# MyPulseSensorTH.net
KiCad netlist of a schematic drawn in EAGLE
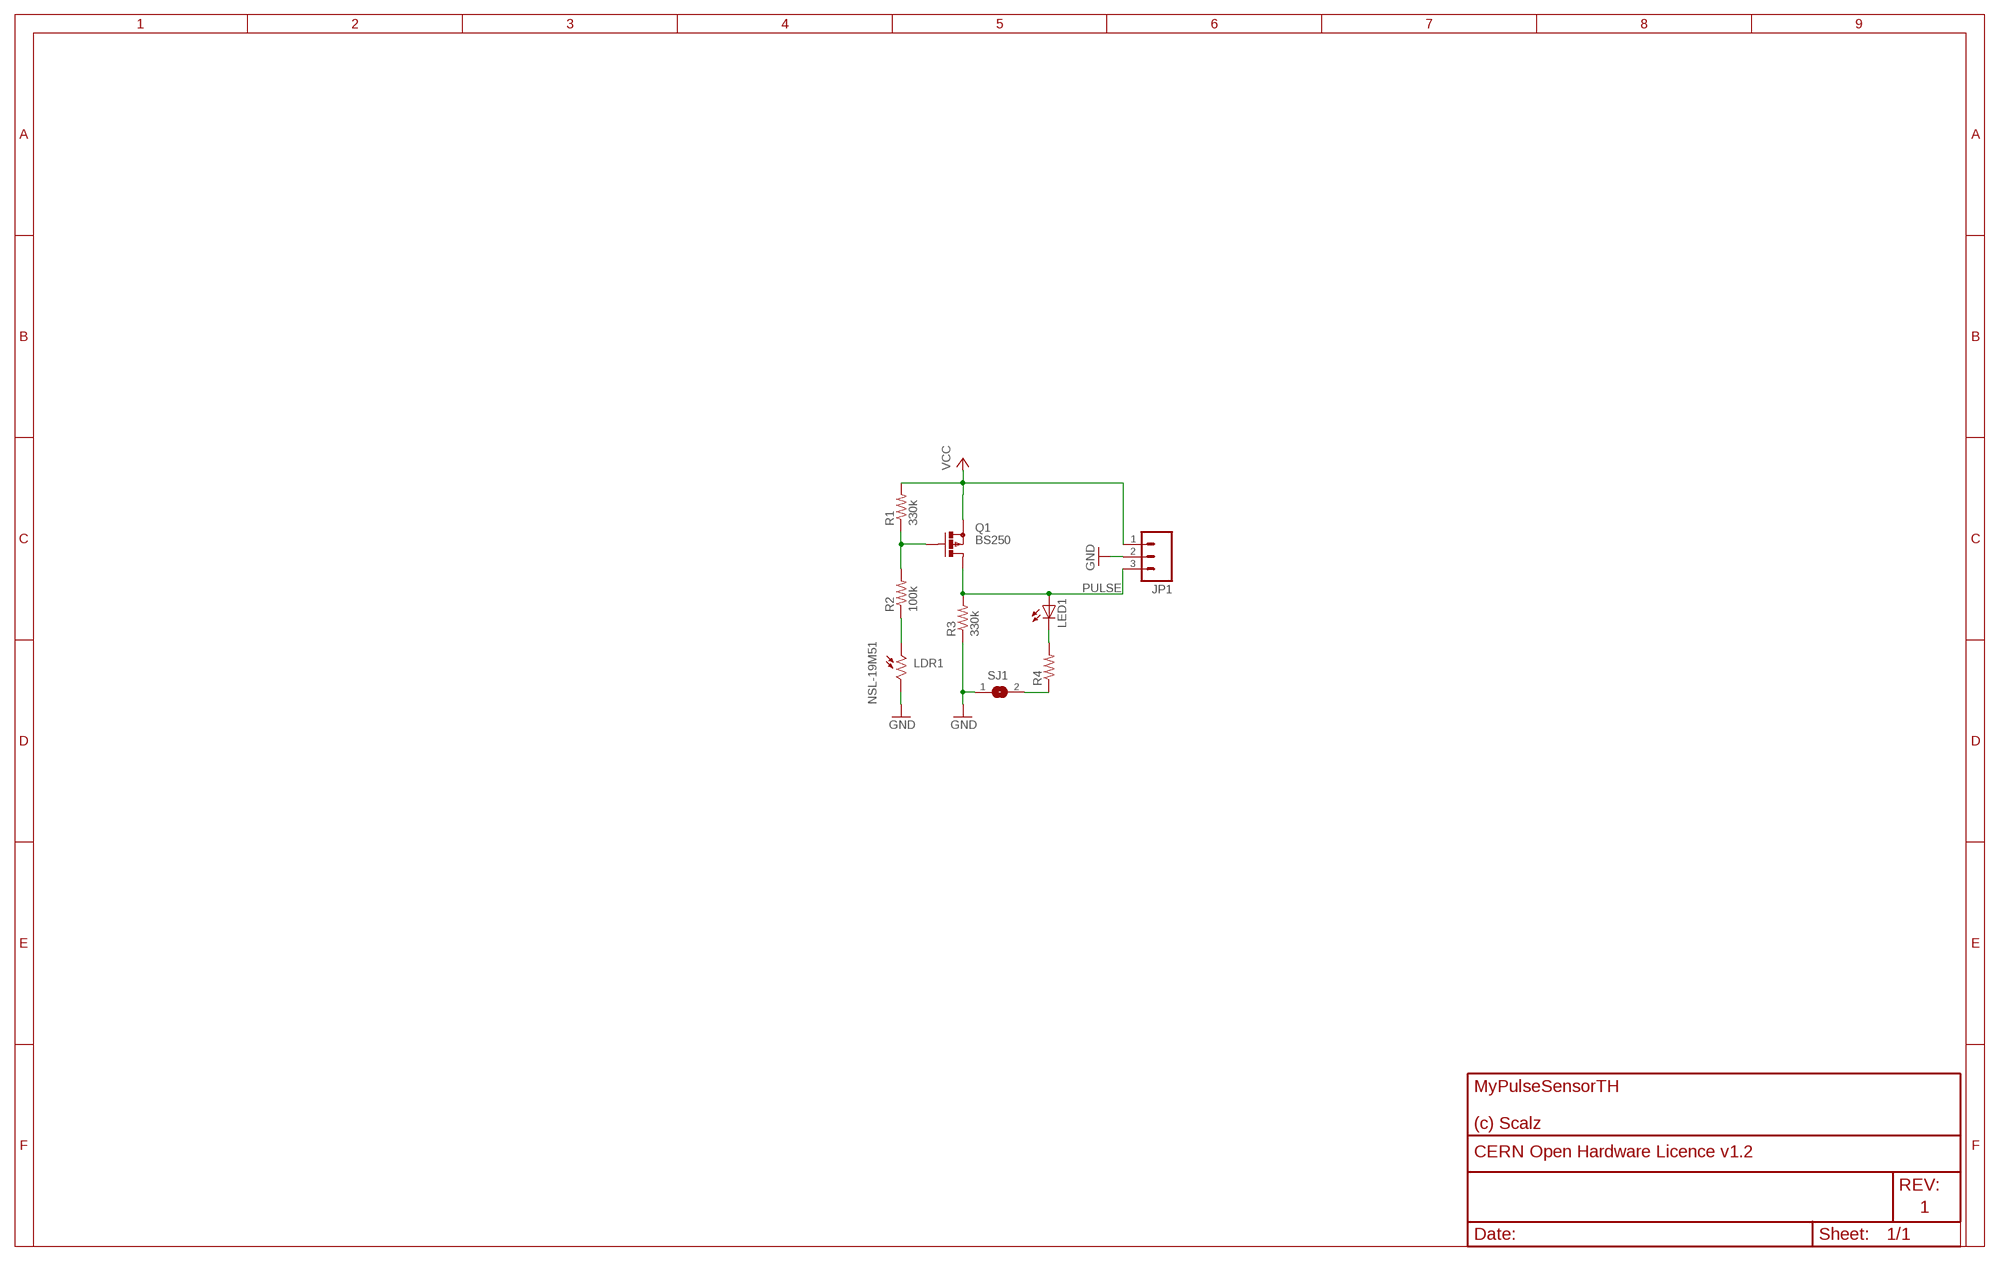
[diagram p0: schematic, sheet 1]

(export (version "E")
  (design (tool "Eeschema 10.0.6"))
  (components
    (comp (ref "JP1")
      (value "M03PTH")
      (footprint "eagle-import:1X03")
      (libsource (lib "eagle-import") (part "M03PTH"))
    )
    (comp (ref "LDR1")
      (value "NSL-19M51")
      (footprint "eagle-import:PHOTORESISTOR_TO18")
      (libsource (lib "eagle-import") (part "NSL-19M51"))
    )
    (comp (ref "LED1")
      (value "LED5MM")
      (footprint "eagle-import:LED5MM")
      (libsource (lib "eagle-import") (part "LED5MM"))
    )
    (comp (ref "Q1")
      (value "BS250")
      (footprint "eagle-import:SOT54E")
      (libsource (lib "eagle-import") (part "BS250"))
    )
    (comp (ref "R1")
      (value "330k")
      (footprint "eagle-import:RESISTOR_TH")
      (libsource (lib "eagle-import") (part "RESISTOR"))
    )
    (comp (ref "R2")
      (value "100k")
      (footprint "eagle-import:RESISTOR_TH")
      (libsource (lib "eagle-import") (part "RESISTOR"))
    )
    (comp (ref "R3")
      (value "330k")
      (footprint "eagle-import:RESISTOR_TH")
      (libsource (lib "eagle-import") (part "RESISTOR"))
    )
    (comp (ref "R4")
      (value "RESISTOR")
      (footprint "eagle-import:RESISTOR_TH")
      (libsource (lib "eagle-import") (part "RESISTOR"))
    )
    (comp (ref "SJ1") (value "SJ") (footprint "eagle-import:SJ") (libsource (lib "eagle-import") (part "SJ")))
  )
  (nets
    (net (code "1") (name "/PULSE") (class "Default")
      (node (ref "JP1") (pin "3") (pinfunction "3_3") (pintype "passive"))
      (node (ref "LED1") (pin "A") (pinfunction "A_A") (pintype "passive"))
      (node (ref "Q1") (pin "D") (pinfunction "D_D") (pintype "passive"))
      (node (ref "R3") (pin "2") (pinfunction "2_2") (pintype "passive"))
    )
    (net (code "2") (name "GND") (class "Default")
      (node (ref "JP1") (pin "2") (pinfunction "2_2") (pintype "passive"))
      (node (ref "LDR1") (pin "2") (pinfunction "2_2") (pintype "passive"))
      (node (ref "R3") (pin "1") (pinfunction "1_1") (pintype "passive"))
      (node (ref "SJ1") (pin "1") (pinfunction "1_1") (pintype "passive"))
    )
    (net (code "3") (name "Net-(LDR1-Pad1)") (class "Default")
      (node (ref "LDR1") (pin "1") (pinfunction "1_1") (pintype "passive"))
      (node (ref "R2") (pin "1") (pinfunction "1_1") (pintype "passive"))
    )
    (net (code "4") (name "Net-(LED1-C)") (class "Default")
      (node (ref "LED1") (pin "K") (pinfunction "C_K") (pintype "passive"))
      (node (ref "R4") (pin "2") (pinfunction "2_2") (pintype "passive"))
    )
    (net (code "5") (name "Net-(Q1-PadG)") (class "Default")
      (node (ref "Q1") (pin "G") (pinfunction "G_G") (pintype "passive"))
      (node (ref "R1") (pin "1") (pinfunction "1_1") (pintype "passive"))
      (node (ref "R2") (pin "2") (pinfunction "2_2") (pintype "passive"))
    )
    (net (code "6") (name "Net-(R4-Pad1)") (class "Default")
      (node (ref "R4") (pin "1") (pinfunction "1_1") (pintype "passive"))
      (node (ref "SJ1") (pin "2") (pinfunction "2_2") (pintype "passive"))
    )
    (net (code "7") (name "VCC") (class "Default")
      (node (ref "JP1") (pin "1") (pinfunction "1_1") (pintype "passive"))
      (node (ref "Q1") (pin "S") (pinfunction "S_S") (pintype "passive"))
      (node (ref "R1") (pin "2") (pinfunction "2_2") (pintype "passive"))
    )
  )
)
